# output_8ch_spi_mux.net
KiCad netlist of a schematic drawn in EAGLE
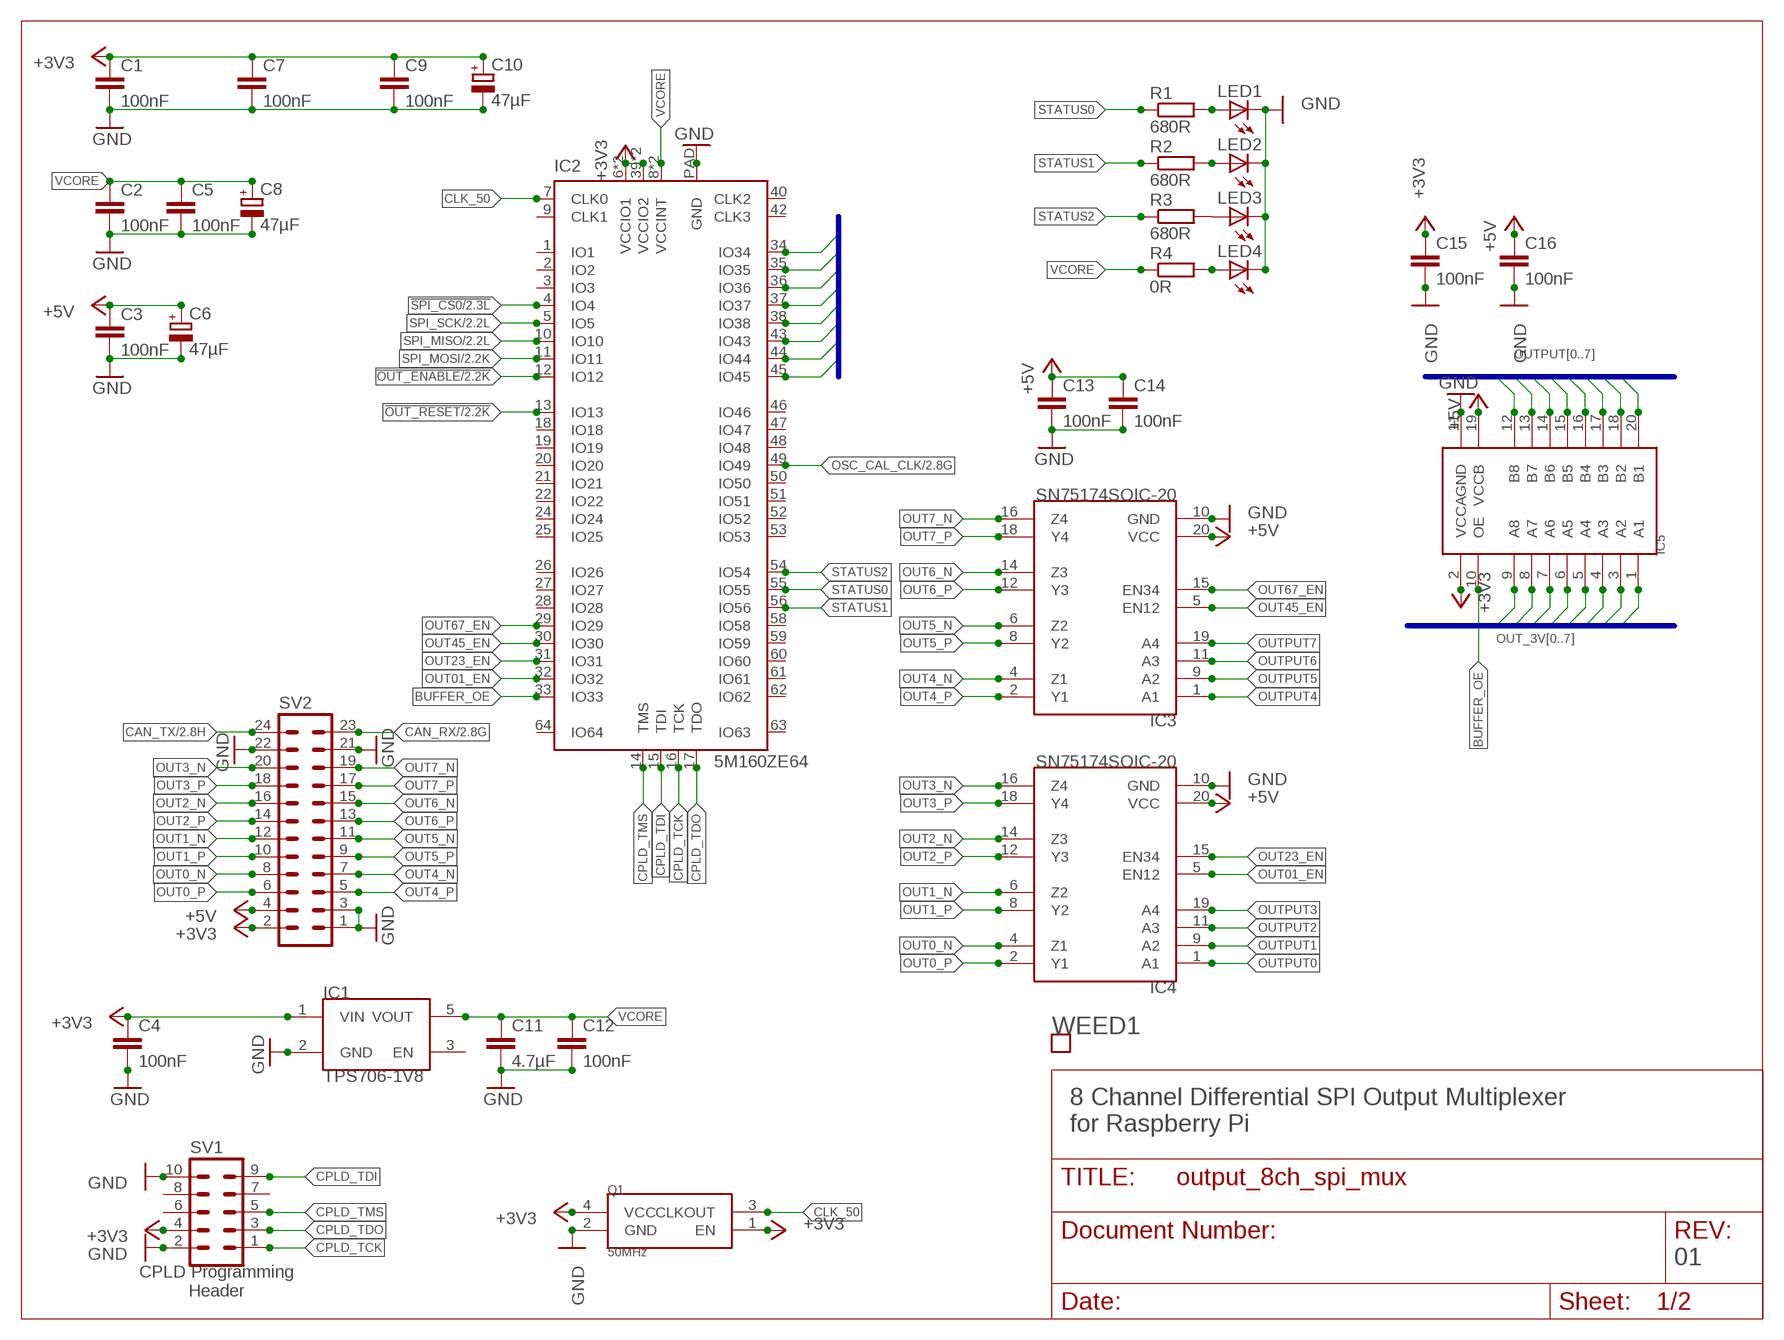
[diagram p0: schematic, sheet 1]
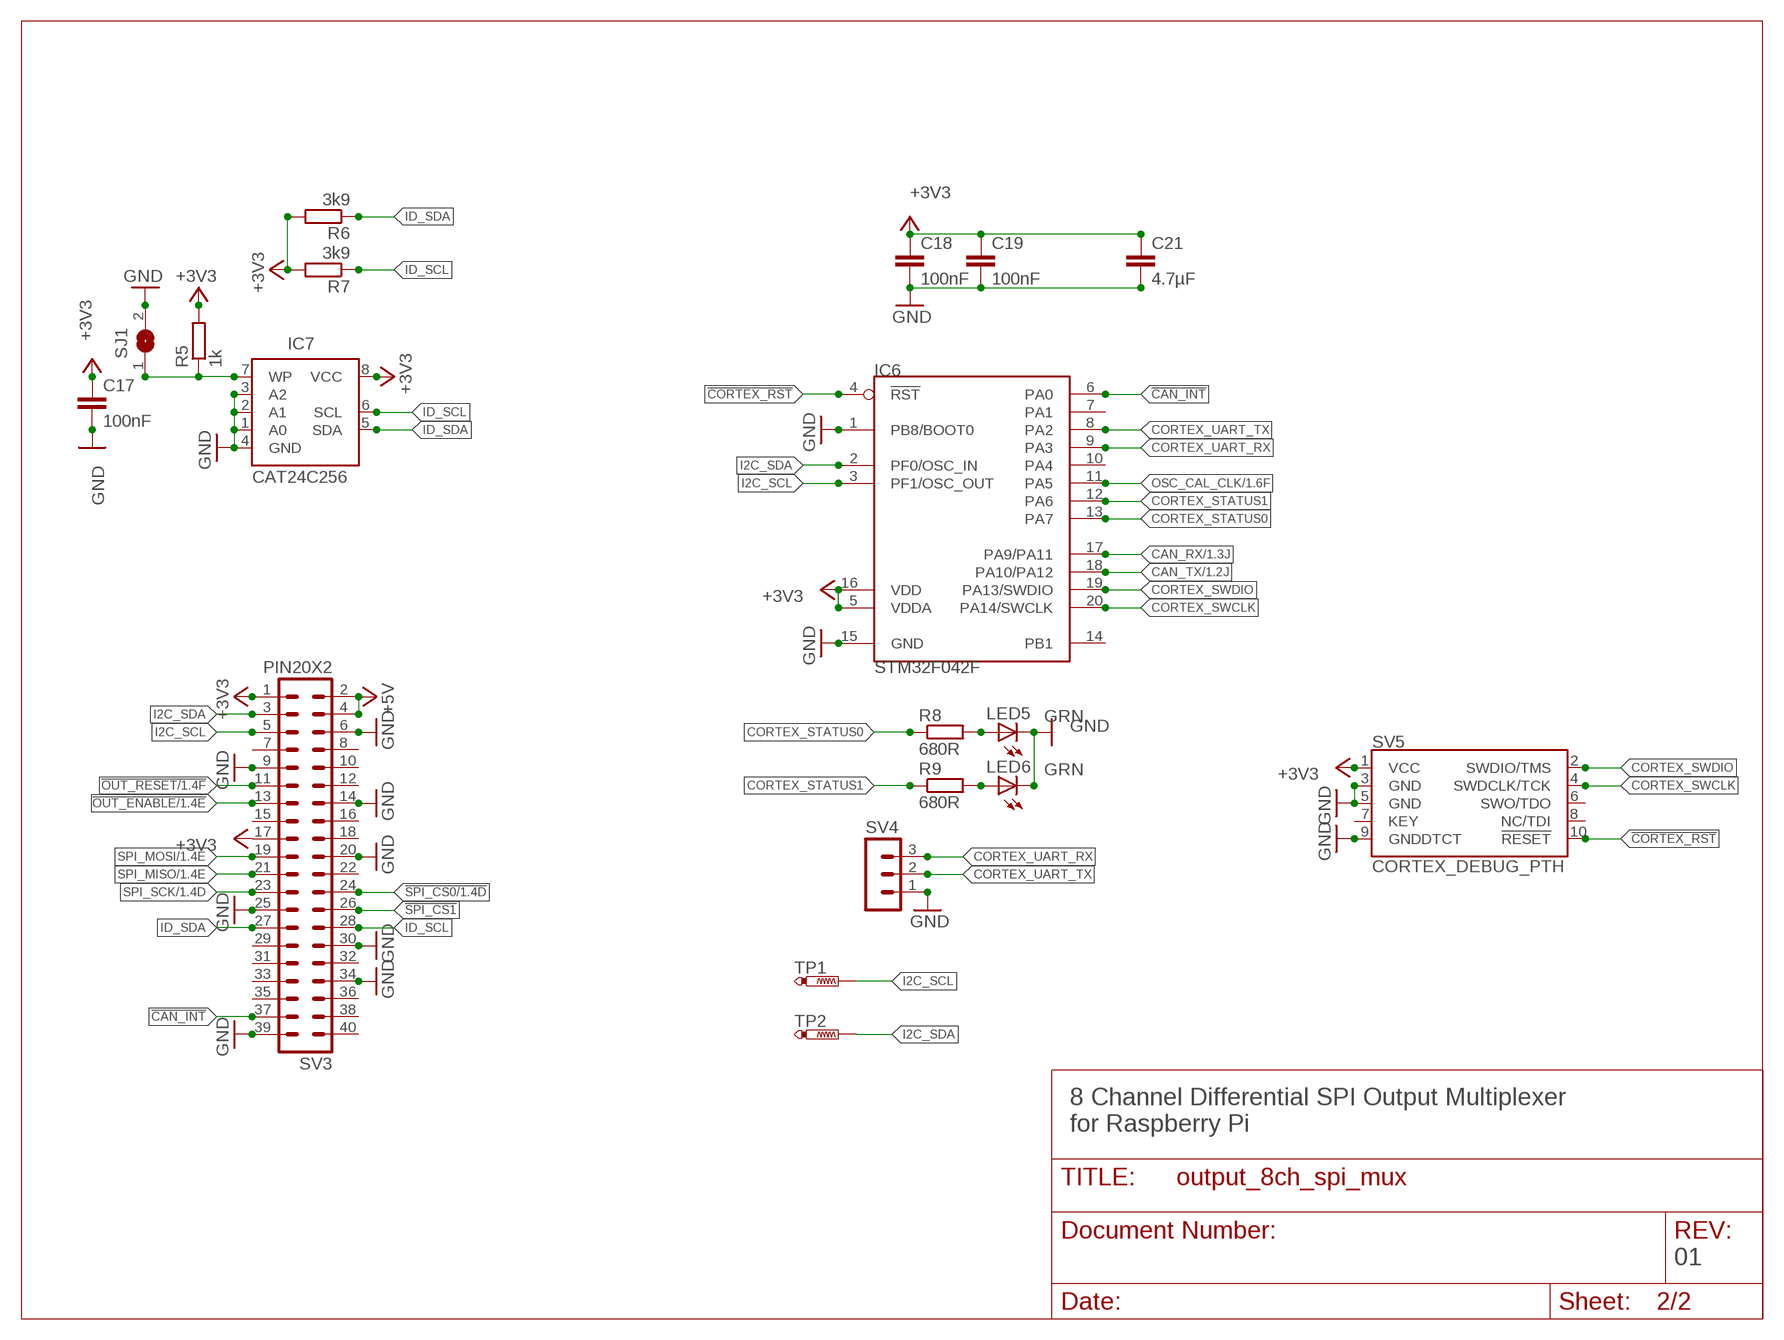
[diagram p1: schematic, sheet 2]

(export (version "E")
  (design (tool "Eeschema 10.0.6"))
  (components
    (comp (ref "C1")
      (value "100nF")
      (footprint "eagle-import:C0805")
      (libsource (lib "eagle-import") (part "C-EUC0805"))
    )
    (comp (ref "C2")
      (value "100nF")
      (footprint "eagle-import:C0805")
      (libsource (lib "eagle-import") (part "C-EUC0805"))
    )
    (comp (ref "C3")
      (value "100nF")
      (footprint "eagle-import:C0805")
      (libsource (lib "eagle-import") (part "C-EUC0805"))
    )
    (comp (ref "C4")
      (value "100nF")
      (footprint "eagle-import:C0805")
      (libsource (lib "eagle-import") (part "C-EUC0805"))
    )
    (comp (ref "C5")
      (value "100nF")
      (footprint "eagle-import:C0805")
      (libsource (lib "eagle-import") (part "C-EUC0805"))
    )
    (comp (ref "C6")
      (value "47µF")
      (footprint "eagle-import:CT6032")
      (libsource (lib "eagle-import") (part "CPOL-EUCT6032"))
    )
    (comp (ref "C7")
      (value "100nF")
      (footprint "eagle-import:C0805")
      (libsource (lib "eagle-import") (part "C-EUC0805"))
    )
    (comp (ref "C8")
      (value "47µF")
      (footprint "eagle-import:CT6032")
      (libsource (lib "eagle-import") (part "CPOL-EUCT6032"))
    )
    (comp (ref "C9")
      (value "100nF")
      (footprint "eagle-import:C0805")
      (libsource (lib "eagle-import") (part "C-EUC0805"))
    )
    (comp (ref "C10")
      (value "47µF")
      (footprint "eagle-import:CT6032")
      (libsource (lib "eagle-import") (part "CPOL-EUCT6032"))
    )
    (comp (ref "C11")
      (value "4.7µF")
      (footprint "eagle-import:C0805")
      (libsource (lib "eagle-import") (part "C-EUC0805"))
    )
    (comp (ref "C12")
      (value "100nF")
      (footprint "eagle-import:C0805")
      (libsource (lib "eagle-import") (part "C-EUC0805"))
    )
    (comp (ref "C13")
      (value "100nF")
      (footprint "eagle-import:C0805")
      (libsource (lib "eagle-import") (part "C-EUC0805"))
    )
    (comp (ref "C14")
      (value "100nF")
      (footprint "eagle-import:C0805")
      (libsource (lib "eagle-import") (part "C-EUC0805"))
    )
    (comp (ref "C15")
      (value "100nF")
      (footprint "eagle-import:C0805")
      (libsource (lib "eagle-import") (part "C-EUC0805"))
    )
    (comp (ref "C16")
      (value "100nF")
      (footprint "eagle-import:C0805")
      (libsource (lib "eagle-import") (part "C-EUC0805"))
    )
    (comp (ref "IC1")
      (value "TPS706-1V8")
      (footprint "eagle-import:SOT23-5")
      (libsource (lib "eagle-import") (part "TPS706SOT23-5"))
    )
    (comp (ref "IC2")
      (value "5M160ZE64")
      (footprint "eagle-import:EQFP64")
      (libsource (lib "eagle-import") (part "5M160ZE64"))
    )
    (comp (ref "IC3")
      (value "SN75174SOIC-20")
      (footprint "eagle-import:SOIC20S")
      (libsource (lib "eagle-import") (part "SN75174SOIC-20"))
    )
    (comp (ref "IC4")
      (value "SN75174SOIC-20")
      (footprint "eagle-import:SOIC20S")
      (libsource (lib "eagle-import") (part "SN75174SOIC-20"))
    )
    (comp (ref "IC5")
      (value "TXB0108TSSOP20")
      (footprint "eagle-import:TSSOP20")
      (libsource (lib "eagle-import") (part "TXB0108TSSOP20"))
    )
    (comp (ref "LED1")
      (value "LEDCHIPLED_1206")
      (footprint "eagle-import:CHIPLED_1206")
      (libsource (lib "eagle-import") (part "LEDCHIPLED_1206"))
    )
    (comp (ref "LED2")
      (value "LEDCHIPLED_1206")
      (footprint "eagle-import:CHIPLED_1206")
      (libsource (lib "eagle-import") (part "LEDCHIPLED_1206"))
    )
    (comp (ref "LED3")
      (value "LEDCHIPLED_1206")
      (footprint "eagle-import:CHIPLED_1206")
      (libsource (lib "eagle-import") (part "LEDCHIPLED_1206"))
    )
    (comp (ref "LED4")
      (value "LEDCHIPLED_1206")
      (footprint "eagle-import:CHIPLED_1206")
      (libsource (lib "eagle-import") (part "LEDCHIPLED_1206"))
    )
    (comp (ref "Q1")
      (value "50MHz")
      (footprint "eagle-import:VLGA-4")
      (libsource (lib "eagle-import") (part "DSC61XX"))
    )
    (comp (ref "R1")
      (value "680R")
      (footprint "eagle-import:M0805")
      (libsource (lib "eagle-import") (part "R-EU_M0805"))
    )
    (comp (ref "R2")
      (value "680R")
      (footprint "eagle-import:M0805")
      (libsource (lib "eagle-import") (part "R-EU_M0805"))
    )
    (comp (ref "R3")
      (value "680R")
      (footprint "eagle-import:M0805")
      (libsource (lib "eagle-import") (part "R-EU_M0805"))
    )
    (comp (ref "R4")
      (value "0R")
      (footprint "eagle-import:M0805")
      (libsource (lib "eagle-import") (part "R-EU_M0805"))
    )
    (comp (ref "SV1")
      (value "MA05-2")
      (footprint "eagle-import:MA05-2")
      (libsource (lib "eagle-import") (part "MA05-2"))
    )
    (comp (ref "SV2")
      (value "MA12-2")
      (footprint "eagle-import:MA12-2")
      (libsource (lib "eagle-import") (part "MA12-2"))
    )
    (comp (ref "WEED1")
      (value "WEED")
      (footprint "eagle-import:DOINK")
      (libsource (lib "eagle-import") (part "WEED"))
    )
    (comp (ref "C17")
      (value "100nF")
      (footprint "eagle-import:C0805")
      (libsource (lib "eagle-import") (part "C-EUC0805"))
    )
    (comp (ref "C18")
      (value "100nF")
      (footprint "eagle-import:C0805")
      (libsource (lib "eagle-import") (part "C-EUC0805"))
    )
    (comp (ref "C19")
      (value "100nF")
      (footprint "eagle-import:C0805")
      (libsource (lib "eagle-import") (part "C-EUC0805"))
    )
    (comp (ref "C21")
      (value "4.7µF")
      (footprint "eagle-import:C0805")
      (libsource (lib "eagle-import") (part "C-EUC0805"))
    )
    (comp (ref "IC6")
      (value "STM32F042F")
      (footprint "eagle-import:TSSOP20")
      (libsource (lib "eagle-import") (part "STM32F042F"))
    )
    (comp (ref "IC7")
      (value "CAT24C256")
      (footprint "eagle-import:SOIC8")
      (libsource (lib "eagle-import") (part "EEPROM24"))
    )
    (comp (ref "LED5")
      (value "GRN")
      (footprint "eagle-import:CHIPLED_1206")
      (libsource (lib "eagle-import") (part "LEDCHIPLED_1206"))
    )
    (comp (ref "LED6")
      (value "GRN")
      (footprint "eagle-import:CHIPLED_1206")
      (libsource (lib "eagle-import") (part "LEDCHIPLED_1206"))
    )
    (comp (ref "R5")
      (value "1k")
      (footprint "eagle-import:M0805")
      (libsource (lib "eagle-import") (part "R-EU_M0805"))
    )
    (comp (ref "R6")
      (value "3k9")
      (footprint "eagle-import:M0805")
      (libsource (lib "eagle-import") (part "R-EU_M0805"))
    )
    (comp (ref "R7")
      (value "3k9")
      (footprint "eagle-import:M0805")
      (libsource (lib "eagle-import") (part "R-EU_M0805"))
    )
    (comp (ref "R8")
      (value "680R")
      (footprint "eagle-import:M0805")
      (libsource (lib "eagle-import") (part "R-EU_M0805"))
    )
    (comp (ref "R9")
      (value "680R")
      (footprint "eagle-import:M0805")
      (libsource (lib "eagle-import") (part "R-EU_M0805"))
    )
    (comp (ref "SJ1") (value "SJ") (footprint "eagle-import:SJ") (libsource (lib "eagle-import") (part "SJ")))
    (comp (ref "SV3")
      (value "PIN20X2")
      (footprint "eagle-import:PIN_20X2")
      (libsource (lib "eagle-import") (part "PIN20X2"))
    )
    (comp (ref "SV4")
      (value "MA03-1")
      (footprint "eagle-import:MA03-1")
      (libsource (lib "eagle-import") (part "MA03-1"))
    )
    (comp (ref "SV5")
      (value "CORTEX_DEBUG_PTH")
      (footprint "eagle-import:2X5-PTH-1.27MM")
      (libsource (lib "eagle-import") (part "CORTEX_DEBUG_PTH"))
    )
    (comp (ref "TP1")
      (value "PTR1B1,27")
      (footprint "eagle-import:B1,27")
      (libsource (lib "eagle-import") (part "PTR1B1,27"))
    )
    (comp (ref "TP2")
      (value "PTR1B1,27")
      (footprint "eagle-import:B1,27")
      (libsource (lib "eagle-import") (part "PTR1B1,27"))
    )
  )
  (nets
    (net (code "1") (name "+3V3") (class "Default")
      (node (ref "C1") (pin "1") (pinfunction "1_1") (pintype "passive"))
      (node (ref "C10") (pin "+") (pinfunction "+_+") (pintype "passive"))
      (node (ref "C15") (pin "1") (pinfunction "1_1") (pintype "passive"))
      (node (ref "C17") (pin "1") (pinfunction "1_1") (pintype "passive"))
      (node (ref "C18") (pin "1") (pinfunction "1_1") (pintype "passive"))
      (node (ref "C19") (pin "1") (pinfunction "1_1") (pintype "passive"))
      (node (ref "C21") (pin "1") (pinfunction "1_1") (pintype "passive"))
      (node (ref "C4") (pin "1") (pinfunction "1_1") (pintype "passive"))
      (node (ref "C7") (pin "1") (pinfunction "1_1") (pintype "passive"))
      (node (ref "C9") (pin "1") (pinfunction "1_1") (pintype "passive"))
      (node (ref "IC1") (pin "1") (pinfunction "VIN_1") (pintype "bidirectional"))
      (node (ref "IC2") (pin "23") (pinfunction "VCCIO1_23") (pintype "power_in"))
      (node (ref "IC2") (pin "39") (pinfunction "VCCIO2_39") (pintype "power_in"))
      (node (ref "IC2") (pin "57") (pinfunction "VCCIO2_57") (pintype "power_in"))
      (node (ref "IC2") (pin "6") (pinfunction "VCCIO1_6") (pintype "power_in"))
      (node (ref "IC5") (pin "2") (pinfunction "VCCA_2") (pintype "bidirectional"))
      (node (ref "IC6") (pin "16") (pinfunction "VDD_16") (pintype "power_in"))
      (node (ref "IC6") (pin "5") (pinfunction "VDDA_5") (pintype "power_in"))
      (node (ref "IC7") (pin "8") (pinfunction "VCC_8") (pintype "power_in"))
      (node (ref "Q1") (pin "1") (pinfunction "EN_1") (pintype "bidirectional"))
      (node (ref "Q1") (pin "4") (pinfunction "VCC_4") (pintype "power_in"))
      (node (ref "R5") (pin "2") (pinfunction "2_2") (pintype "passive"))
      (node (ref "R6") (pin "2") (pinfunction "2_2") (pintype "passive"))
      (node (ref "R7") (pin "2") (pinfunction "2_2") (pintype "passive"))
      (node (ref "SV1") (pin "4") (pinfunction "4_4") (pintype "passive"))
      (node (ref "SV2") (pin "2") (pinfunction "2_2") (pintype "passive"))
      (node (ref "SV3") (pin "1") (pinfunction "1_1") (pintype "passive"))
      (node (ref "SV3") (pin "17") (pinfunction "17_17") (pintype "passive"))
      (node (ref "SV5") (pin "1") (pinfunction "VCC_1") (pintype "bidirectional"))
    )
    (net (code "2") (name "+5V") (class "Default")
      (node (ref "C13") (pin "1") (pinfunction "1_1") (pintype "passive"))
      (node (ref "C14") (pin "1") (pinfunction "1_1") (pintype "passive"))
      (node (ref "C16") (pin "1") (pinfunction "1_1") (pintype "passive"))
      (node (ref "C3") (pin "1") (pinfunction "1_1") (pintype "passive"))
      (node (ref "C6") (pin "+") (pinfunction "+_+") (pintype "passive"))
      (node (ref "IC3") (pin "20") (pinfunction "VCC_20") (pintype "power_in"))
      (node (ref "IC4") (pin "20") (pinfunction "VCC_20") (pintype "power_in"))
      (node (ref "IC5") (pin "19") (pinfunction "VCCB_19") (pintype "bidirectional"))
      (node (ref "SV2") (pin "4") (pinfunction "4_4") (pintype "passive"))
      (node (ref "SV3") (pin "2") (pinfunction "2_2") (pintype "passive"))
      (node (ref "SV3") (pin "4") (pinfunction "4_4") (pintype "passive"))
    )
    (net (code "5") (name "BUFFER_OE") (class "Default")
      (node (ref "IC2") (pin "33") (pinfunction "IO33_33") (pintype "bidirectional"))
      (node (ref "IC5") (pin "10") (pinfunction "OE_10") (pintype "bidirectional"))
    )
    (net (code "6") (name "CAN_RX") (class "Default")
      (node (ref "IC6") (pin "17") (pinfunction "PA9/PA11_17") (pintype "bidirectional"))
      (node (ref "SV2") (pin "23") (pinfunction "23_23") (pintype "passive"))
    )
    (net (code "7") (name "CAN_TX") (class "Default")
      (node (ref "IC6") (pin "18") (pinfunction "PA10/PA12_18") (pintype "bidirectional"))
      (node (ref "SV2") (pin "24") (pinfunction "24_24") (pintype "passive"))
    )
    (net (code "8") (name "CLK_50") (class "Default")
      (node (ref "IC2") (pin "7") (pinfunction "CLK0_7") (pintype "bidirectional"))
      (node (ref "Q1") (pin "3") (pinfunction "CLKOUT_3") (pintype "bidirectional"))
    )
    (net (code "9") (name "CORTEX_STATUS0") (class "Default")
      (node (ref "IC6") (pin "13") (pinfunction "PA7_13") (pintype "bidirectional"))
      (node (ref "R8") (pin "1") (pinfunction "1_1") (pintype "passive"))
    )
    (net (code "10") (name "CORTEX_STATUS1") (class "Default")
      (node (ref "IC6") (pin "12") (pinfunction "PA6_12") (pintype "bidirectional"))
      (node (ref "R9") (pin "1") (pinfunction "1_1") (pintype "passive"))
    )
    (net (code "11") (name "CORTEX_SWCLK") (class "Default")
      (node (ref "IC6") (pin "20") (pinfunction "PA14/SWCLK_20") (pintype "bidirectional"))
      (node (ref "SV5") (pin "4") (pinfunction "SWDCLK/TCK_4") (pintype "bidirectional"))
    )
    (net (code "12") (name "CORTEX_SWDIO") (class "Default")
      (node (ref "IC6") (pin "19") (pinfunction "PA13/SWDIO_19") (pintype "bidirectional"))
      (node (ref "SV5") (pin "2") (pinfunction "SWDIO/TMS_2") (pintype "bidirectional"))
    )
    (net (code "13") (name "CORTEX_UART_RX") (class "Default")
      (node (ref "IC6") (pin "9") (pinfunction "PA3_9") (pintype "bidirectional"))
      (node (ref "SV4") (pin "3") (pinfunction "3_3") (pintype "passive"))
    )
    (net (code "14") (name "CORTEX_UART_TX") (class "Default")
      (node (ref "IC6") (pin "8") (pinfunction "PA2_8") (pintype "bidirectional"))
      (node (ref "SV4") (pin "2") (pinfunction "2_2") (pintype "passive"))
    )
    (net (code "15") (name "CPLD_TCK") (class "Default")
      (node (ref "IC2") (pin "16") (pinfunction "TCK_16") (pintype "input"))
      (node (ref "SV1") (pin "1") (pinfunction "1_1") (pintype "passive"))
    )
    (net (code "16") (name "CPLD_TDI") (class "Default")
      (node (ref "IC2") (pin "15") (pinfunction "TDI_15") (pintype "input"))
      (node (ref "SV1") (pin "9") (pinfunction "9_9") (pintype "passive"))
    )
    (net (code "17") (name "CPLD_TDO") (class "Default")
      (node (ref "IC2") (pin "17") (pinfunction "TDO_17") (pintype "output"))
      (node (ref "SV1") (pin "3") (pinfunction "3_3") (pintype "passive"))
    )
    (net (code "18") (name "CPLD_TMS") (class "Default")
      (node (ref "IC2") (pin "14") (pinfunction "TMS_14") (pintype "input"))
      (node (ref "SV1") (pin "5") (pinfunction "5_5") (pintype "passive"))
    )
    (net (code "19") (name "GND") (class "Default")
      (node (ref "C1") (pin "2") (pinfunction "2_2") (pintype "passive"))
      (node (ref "C10") (pin "-") (pinfunction "-_-") (pintype "passive"))
      (node (ref "C11") (pin "2") (pinfunction "2_2") (pintype "passive"))
      (node (ref "C12") (pin "2") (pinfunction "2_2") (pintype "passive"))
      (node (ref "C13") (pin "2") (pinfunction "2_2") (pintype "passive"))
      (node (ref "C14") (pin "2") (pinfunction "2_2") (pintype "passive"))
      (node (ref "C15") (pin "2") (pinfunction "2_2") (pintype "passive"))
      (node (ref "C16") (pin "2") (pinfunction "2_2") (pintype "passive"))
      (node (ref "C17") (pin "2") (pinfunction "2_2") (pintype "passive"))
      (node (ref "C18") (pin "2") (pinfunction "2_2") (pintype "passive"))
      (node (ref "C19") (pin "2") (pinfunction "2_2") (pintype "passive"))
      (node (ref "C2") (pin "2") (pinfunction "2_2") (pintype "passive"))
      (node (ref "C21") (pin "2") (pinfunction "2_2") (pintype "passive"))
      (node (ref "C3") (pin "2") (pinfunction "2_2") (pintype "passive"))
      (node (ref "C4") (pin "2") (pinfunction "2_2") (pintype "passive"))
      (node (ref "C5") (pin "2") (pinfunction "2_2") (pintype "passive"))
      (node (ref "C6") (pin "-") (pinfunction "-_-") (pintype "passive"))
      (node (ref "C7") (pin "2") (pinfunction "2_2") (pintype "passive"))
      (node (ref "C8") (pin "-") (pinfunction "-_-") (pintype "passive"))
      (node (ref "C9") (pin "2") (pinfunction "2_2") (pintype "passive"))
      (node (ref "IC1") (pin "2") (pinfunction "GND_2") (pintype "bidirectional"))
      (node (ref "IC2") (pin "PAD") (pinfunction "GND_PAD") (pintype "power_in"))
      (node (ref "IC3") (pin "10") (pinfunction "GND_10") (pintype "power_in"))
      (node (ref "IC4") (pin "10") (pinfunction "GND_10") (pintype "power_in"))
      (node (ref "IC5") (pin "11") (pinfunction "GND_11") (pintype "bidirectional"))
      (node (ref "IC6") (pin "1") (pinfunction "PB8/BOOT0_1") (pintype "bidirectional"))
      (node (ref "IC6") (pin "15") (pinfunction "GND_15") (pintype "power_in"))
      (node (ref "IC7") (pin "1") (pinfunction "A0_1") (pintype "input"))
      (node (ref "IC7") (pin "2") (pinfunction "A1_2") (pintype "input"))
      (node (ref "IC7") (pin "3") (pinfunction "A2_3") (pintype "input"))
      (node (ref "IC7") (pin "4") (pinfunction "GND_4") (pintype "power_in"))
      (node (ref "LED1") (pin "C") (pinfunction "C_C") (pintype "passive"))
      (node (ref "LED2") (pin "C") (pinfunction "C_C") (pintype "passive"))
      (node (ref "LED3") (pin "C") (pinfunction "C_C") (pintype "passive"))
      (node (ref "LED4") (pin "C") (pinfunction "C_C") (pintype "passive"))
      (node (ref "LED5") (pin "C") (pinfunction "C_C") (pintype "passive"))
      (node (ref "LED6") (pin "C") (pinfunction "C_C") (pintype "passive"))
      (node (ref "Q1") (pin "2") (pinfunction "GND_2") (pintype "power_in"))
      (node (ref "SJ1") (pin "2") (pinfunction "2_2") (pintype "passive"))
      (node (ref "SV1") (pin "10") (pinfunction "10_10") (pintype "passive"))
      (node (ref "SV1") (pin "2") (pinfunction "2_2") (pintype "passive"))
      (node (ref "SV2") (pin "1") (pinfunction "1_1") (pintype "passive"))
      (node (ref "SV2") (pin "21") (pinfunction "21_21") (pintype "passive"))
      (node (ref "SV2") (pin "22") (pinfunction "22_22") (pintype "passive"))
      (node (ref "SV2") (pin "3") (pinfunction "3_3") (pintype "passive"))
      (node (ref "SV3") (pin "14") (pinfunction "14_14") (pintype "passive"))
      (node (ref "SV3") (pin "20") (pinfunction "20_20") (pintype "passive"))
      (node (ref "SV3") (pin "25") (pinfunction "25_25") (pintype "passive"))
      (node (ref "SV3") (pin "30") (pinfunction "30_30") (pintype "passive"))
      (node (ref "SV3") (pin "34") (pinfunction "34_34") (pintype "passive"))
      (node (ref "SV3") (pin "39") (pinfunction "39_39") (pintype "passive"))
      (node (ref "SV3") (pin "6") (pinfunction "6_6") (pintype "passive"))
      (node (ref "SV3") (pin "9") (pinfunction "9_9") (pintype "passive"))
      (node (ref "SV4") (pin "1") (pinfunction "1_1") (pintype "passive"))
      (node (ref "SV5") (pin "3") (pinfunction "GND_3") (pintype "bidirectional"))
      (node (ref "SV5") (pin "5") (pinfunction "GND_5") (pintype "bidirectional"))
      (node (ref "SV5") (pin "9") (pinfunction "GNDDTCT_9") (pintype "bidirectional"))
    )
    (net (code "20") (name "I2C_SCL") (class "Default")
      (node (ref "IC6") (pin "3") (pinfunction "PF1/OSC_OUT_3") (pintype "bidirectional"))
      (node (ref "SV3") (pin "5") (pinfunction "5_5") (pintype "passive"))
      (node (ref "TP1") (pin "TP") (pinfunction "TP_TP") (pintype "input"))
    )
    (net (code "21") (name "I2C_SDA") (class "Default")
      (node (ref "IC6") (pin "2") (pinfunction "PF0/OSC_IN_2") (pintype "bidirectional"))
      (node (ref "SV3") (pin "3") (pinfunction "3_3") (pintype "passive"))
      (node (ref "TP2") (pin "TP") (pinfunction "TP_TP") (pintype "input"))
    )
    (net (code "22") (name "ID_SCL") (class "Default")
      (node (ref "IC7") (pin "6") (pinfunction "SCL_6") (pintype "input"))
      (node (ref "R7") (pin "1") (pinfunction "1_1") (pintype "passive"))
      (node (ref "SV3") (pin "28") (pinfunction "28_28") (pintype "passive"))
    )
    (net (code "23") (name "ID_SDA") (class "Default")
      (node (ref "IC7") (pin "5") (pinfunction "SDA_5") (pintype "bidirectional"))
      (node (ref "R6") (pin "1") (pinfunction "1_1") (pintype "passive"))
      (node (ref "SV3") (pin "27") (pinfunction "27_27") (pintype "passive"))
    )
    (net (code "24") (name "Net-(IC7-WP)") (class "Default")
      (node (ref "IC7") (pin "7") (pinfunction "WP_7") (pintype "input"))
      (node (ref "R5") (pin "1") (pinfunction "1_1") (pintype "passive"))
      (node (ref "SJ1") (pin "1") (pinfunction "1_1") (pintype "passive"))
    )
    (net (code "25") (name "Net-(LED1-PadA)") (class "Default")
      (node (ref "LED1") (pin "A") (pinfunction "A_A") (pintype "passive"))
      (node (ref "R1") (pin "2") (pinfunction "2_2") (pintype "passive"))
    )
    (net (code "26") (name "Net-(LED2-PadA)") (class "Default")
      (node (ref "LED2") (pin "A") (pinfunction "A_A") (pintype "passive"))
      (node (ref "R2") (pin "2") (pinfunction "2_2") (pintype "passive"))
    )
    (net (code "27") (name "Net-(LED3-PadA)") (class "Default")
      (node (ref "LED3") (pin "A") (pinfunction "A_A") (pintype "passive"))
      (node (ref "R3") (pin "2") (pinfunction "2_2") (pintype "passive"))
    )
    (net (code "28") (name "Net-(LED4-PadA)") (class "Default")
      (node (ref "LED4") (pin "A") (pinfunction "A_A") (pintype "passive"))
      (node (ref "R4") (pin "2") (pinfunction "2_2") (pintype "passive"))
    )
    (net (code "29") (name "Net-(LED5-PadA)") (class "Default")
      (node (ref "LED5") (pin "A") (pinfunction "A_A") (pintype "passive"))
      (node (ref "R8") (pin "2") (pinfunction "2_2") (pintype "passive"))
    )
    (net (code "30") (name "Net-(LED6-PadA)") (class "Default")
      (node (ref "LED6") (pin "A") (pinfunction "A_A") (pintype "passive"))
      (node (ref "R9") (pin "2") (pinfunction "2_2") (pintype "passive"))
    )
    (net (code "31") (name "OSC_CAL_CLK") (class "Default")
      (node (ref "IC2") (pin "49") (pinfunction "IO49_49") (pintype "bidirectional"))
      (node (ref "IC6") (pin "11") (pinfunction "PA5_11") (pintype "bidirectional"))
    )
    (net (code "32") (name "OUT0_N") (class "Default")
      (node (ref "IC4") (pin "4") (pinfunction "Z1_4") (pintype "output"))
      (node (ref "SV2") (pin "8") (pinfunction "8_8") (pintype "passive"))
    )
    (net (code "33") (name "OUT0_P") (class "Default")
      (node (ref "IC4") (pin "2") (pinfunction "Y1_2") (pintype "output"))
      (node (ref "SV2") (pin "6") (pinfunction "6_6") (pintype "passive"))
    )
    (net (code "34") (name "OUT01_EN") (class "Default")
      (node (ref "IC2") (pin "32") (pinfunction "IO32_32") (pintype "bidirectional"))
      (node (ref "IC4") (pin "5") (pinfunction "EN12_5") (pintype "input"))
    )
    (net (code "35") (name "OUT1_N") (class "Default")
      (node (ref "IC4") (pin "6") (pinfunction "Z2_6") (pintype "output"))
      (node (ref "SV2") (pin "12") (pinfunction "12_12") (pintype "passive"))
    )
    (net (code "36") (name "OUT1_P") (class "Default")
      (node (ref "IC4") (pin "8") (pinfunction "Y2_8") (pintype "output"))
      (node (ref "SV2") (pin "10") (pinfunction "10_10") (pintype "passive"))
    )
    (net (code "37") (name "OUT2_N") (class "Default")
      (node (ref "IC4") (pin "14") (pinfunction "Z3_14") (pintype "output"))
      (node (ref "SV2") (pin "16") (pinfunction "16_16") (pintype "passive"))
    )
    (net (code "38") (name "OUT2_P") (class "Default")
      (node (ref "IC4") (pin "12") (pinfunction "Y3_12") (pintype "output"))
      (node (ref "SV2") (pin "14") (pinfunction "14_14") (pintype "passive"))
    )
    (net (code "39") (name "OUT3_N") (class "Default")
      (node (ref "IC4") (pin "16") (pinfunction "Z4_16") (pintype "output"))
      (node (ref "SV2") (pin "20") (pinfunction "20_20") (pintype "passive"))
    )
    (net (code "40") (name "OUT3_P") (class "Default")
      (node (ref "IC4") (pin "18") (pinfunction "Y4_18") (pintype "output"))
      (node (ref "SV2") (pin "18") (pinfunction "18_18") (pintype "passive"))
    )
    (net (code "41") (name "OUT4_N") (class "Default")
      (node (ref "IC3") (pin "4") (pinfunction "Z1_4") (pintype "output"))
      (node (ref "SV2") (pin "7") (pinfunction "7_7") (pintype "passive"))
    )
    (net (code "42") (name "OUT4_P") (class "Default")
      (node (ref "IC3") (pin "2") (pinfunction "Y1_2") (pintype "output"))
      (node (ref "SV2") (pin "5") (pinfunction "5_5") (pintype "passive"))
    )
    (net (code "43") (name "OUT5_N") (class "Default")
      (node (ref "IC3") (pin "6") (pinfunction "Z2_6") (pintype "output"))
      (node (ref "SV2") (pin "11") (pinfunction "11_11") (pintype "passive"))
    )
    (net (code "44") (name "OUT5_P") (class "Default")
      (node (ref "IC3") (pin "8") (pinfunction "Y2_8") (pintype "output"))
      (node (ref "SV2") (pin "9") (pinfunction "9_9") (pintype "passive"))
    )
    (net (code "45") (name "OUT6_N") (class "Default")
      (node (ref "IC3") (pin "14") (pinfunction "Z3_14") (pintype "output"))
      (node (ref "SV2") (pin "15") (pinfunction "15_15") (pintype "passive"))
    )
    (net (code "46") (name "OUT6_P") (class "Default")
      (node (ref "IC3") (pin "12") (pinfunction "Y3_12") (pintype "output"))
      (node (ref "SV2") (pin "13") (pinfunction "13_13") (pintype "passive"))
    )
    (net (code "47") (name "OUT7_N") (class "Default")
      (node (ref "IC3") (pin "16") (pinfunction "Z4_16") (pintype "output"))
      (node (ref "SV2") (pin "19") (pinfunction "19_19") (pintype "passive"))
    )
    (net (code "48") (name "OUT7_P") (class "Default")
      (node (ref "IC3") (pin "18") (pinfunction "Y4_18") (pintype "output"))
      (node (ref "SV2") (pin "17") (pinfunction "17_17") (pintype "passive"))
    )
    (net (code "49") (name "OUT23_EN") (class "Default")
      (node (ref "IC2") (pin "31") (pinfunction "IO31_31") (pintype "bidirectional"))
      (node (ref "IC4") (pin "15") (pinfunction "EN34_15") (pintype "input"))
    )
    (net (code "50") (name "OUT45_EN") (class "Default")
      (node (ref "IC2") (pin "30") (pinfunction "IO30_30") (pintype "bidirectional"))
      (node (ref "IC3") (pin "5") (pinfunction "EN12_5") (pintype "input"))
    )
    (net (code "51") (name "OUT67_EN") (class "Default")
      (node (ref "IC2") (pin "29") (pinfunction "IO29_29") (pintype "bidirectional"))
      (node (ref "IC3") (pin "15") (pinfunction "EN34_15") (pintype "input"))
    )
    (net (code "52") (name "OUTPUT0") (class "Default")
      (node (ref "IC4") (pin "1") (pinfunction "A1_1") (pintype "input"))
      (node (ref "IC5") (pin "20") (pinfunction "B1_20") (pintype "bidirectional"))
    )
    (net (code "53") (name "OUTPUT1") (class "Default")
      (node (ref "IC4") (pin "9") (pinfunction "A2_9") (pintype "input"))
      (node (ref "IC5") (pin "18") (pinfunction "B2_18") (pintype "bidirectional"))
    )
    (net (code "54") (name "OUTPUT2") (class "Default")
      (node (ref "IC4") (pin "11") (pinfunction "A3_11") (pintype "input"))
      (node (ref "IC5") (pin "17") (pinfunction "B3_17") (pintype "bidirectional"))
    )
    (net (code "55") (name "OUTPUT3") (class "Default")
      (node (ref "IC4") (pin "19") (pinfunction "A4_19") (pintype "input"))
      (node (ref "IC5") (pin "16") (pinfunction "B4_16") (pintype "bidirectional"))
    )
    (net (code "56") (name "OUTPUT4") (class "Default")
      (node (ref "IC3") (pin "1") (pinfunction "A1_1") (pintype "input"))
      (node (ref "IC5") (pin "15") (pinfunction "B5_15") (pintype "bidirectional"))
    )
    (net (code "57") (name "OUTPUT5") (class "Default")
      (node (ref "IC3") (pin "9") (pinfunction "A2_9") (pintype "input"))
      (node (ref "IC5") (pin "14") (pinfunction "B6_14") (pintype "bidirectional"))
    )
    (net (code "58") (name "OUTPUT6") (class "Default")
      (node (ref "IC3") (pin "11") (pinfunction "A3_11") (pintype "input"))
      (node (ref "IC5") (pin "13") (pinfunction "B7_13") (pintype "bidirectional"))
    )
    (net (code "59") (name "OUTPUT7") (class "Default")
      (node (ref "IC3") (pin "19") (pinfunction "A4_19") (pintype "input"))
      (node (ref "IC5") (pin "12") (pinfunction "B8_12") (pintype "bidirectional"))
    )
    (net (code "60") (name "OUT_3V0") (class "Default")
      (node (ref "IC2") (pin "45") (pinfunction "IO45_45") (pintype "bidirectional"))
      (node (ref "IC5") (pin "1") (pinfunction "A1_1") (pintype "bidirectional"))
    )
    (net (code "61") (name "OUT_3V1") (class "Default")
      (node (ref "IC2") (pin "44") (pinfunction "IO44_44") (pintype "bidirectional"))
      (node (ref "IC5") (pin "3") (pinfunction "A2_3") (pintype "bidirectional"))
    )
    (net (code "62") (name "OUT_3V2") (class "Default")
      (node (ref "IC2") (pin "43") (pinfunction "IO43_43") (pintype "bidirectional"))
      (node (ref "IC5") (pin "4") (pinfunction "A3_4") (pintype "bidirectional"))
    )
    (net (code "63") (name "OUT_3V3") (class "Default")
      (node (ref "IC2") (pin "38") (pinfunction "IO38_38") (pintype "bidirectional"))
      (node (ref "IC5") (pin "5") (pinfunction "A4_5") (pintype "bidirectional"))
    )
    (net (code "64") (name "OUT_3V4") (class "Default")
      (node (ref "IC2") (pin "37") (pinfunction "IO37_37") (pintype "bidirectional"))
      (node (ref "IC5") (pin "6") (pinfunction "A5_6") (pintype "bidirectional"))
    )
    (net (code "65") (name "OUT_3V5") (class "Default")
      (node (ref "IC2") (pin "36") (pinfunction "IO36_36") (pintype "bidirectional"))
      (node (ref "IC5") (pin "7") (pinfunction "A6_7") (pintype "bidirectional"))
    )
    (net (code "66") (name "OUT_3V6") (class "Default")
      (node (ref "IC2") (pin "35") (pinfunction "IO35_35") (pintype "bidirectional"))
      (node (ref "IC5") (pin "8") (pinfunction "A7_8") (pintype "bidirectional"))
    )
    (net (code "67") (name "OUT_3V7") (class "Default")
      (node (ref "IC2") (pin "34") (pinfunction "IO34_34") (pintype "bidirectional"))
      (node (ref "IC5") (pin "9") (pinfunction "A8_9") (pintype "bidirectional"))
    )
    (net (code "68") (name "SPI_MISO") (class "Default")
      (node (ref "IC2") (pin "10") (pinfunction "IO10_10") (pintype "bidirectional"))
      (node (ref "SV3") (pin "21") (pinfunction "21_21") (pintype "passive"))
    )
    (net (code "69") (name "SPI_MOSI") (class "Default")
      (node (ref "IC2") (pin "11") (pinfunction "IO11_11") (pintype "bidirectional"))
      (node (ref "SV3") (pin "19") (pinfunction "19_19") (pintype "passive"))
    )
    (net (code "70") (name "SPI_SCK") (class "Default")
      (node (ref "IC2") (pin "5") (pinfunction "IO5_5") (pintype "bidirectional"))
      (node (ref "SV3") (pin "23") (pinfunction "23_23") (pintype "passive"))
    )
    (net (code "71") (name "STATUS0") (class "Default")
      (node (ref "IC2") (pin "55") (pinfunction "IO55_55") (pintype "bidirectional"))
      (node (ref "R1") (pin "1") (pinfunction "1_1") (pintype "passive"))
    )
    (net (code "72") (name "STATUS1") (class "Default")
      (node (ref "IC2") (pin "56") (pinfunction "IO56_56") (pintype "bidirectional"))
      (node (ref "R2") (pin "1") (pinfunction "1_1") (pintype "passive"))
    )
    (net (code "73") (name "STATUS2") (class "Default")
      (node (ref "IC2") (pin "54") (pinfunction "IO54_54") (pintype "bidirectional"))
      (node (ref "R3") (pin "1") (pinfunction "1_1") (pintype "passive"))
    )
    (net (code "74") (name "VCORE") (class "Default")
      (node (ref "C11") (pin "1") (pinfunction "1_1") (pintype "passive"))
      (node (ref "C12") (pin "1") (pinfunction "1_1") (pintype "passive"))
      (node (ref "C2") (pin "1") (pinfunction "1_1") (pintype "passive"))
      (node (ref "C5") (pin "1") (pinfunction "1_1") (pintype "passive"))
      (node (ref "C8") (pin "+") (pinfunction "+_+") (pintype "passive"))
      (node (ref "IC1") (pin "5") (pinfunction "VOUT_5") (pintype "bidirectional"))
      (node (ref "IC2") (pin "41") (pinfunction "VCCINT_41") (pintype "power_in"))
      (node (ref "IC2") (pin "8") (pinfunction "VCCINT_8") (pintype "power_in"))
      (node (ref "R4") (pin "1") (pinfunction "1_1") (pintype "passive"))
    )
    (net (code "75") (name "unconnected-(IC1-EN-Pad3)") (class "Default")
      (node (ref "IC1") (pin "3") (pinfunction "EN_3") (pintype "bidirectional"))
    )
    (net (code "76") (name "unconnected-(IC2-CLK1-Pad9)") (class "Default")
      (node (ref "IC2") (pin "9") (pinfunction "CLK1_9") (pintype "bidirectional"))
    )
    (net (code "77") (name "unconnected-(IC2-CLK2-Pad40)") (class "Default")
      (node (ref "IC2") (pin "40") (pinfunction "CLK2_40") (pintype "bidirectional"))
    )
    (net (code "78") (name "unconnected-(IC2-CLK3-Pad42)") (class "Default")
      (node (ref "IC2") (pin "42") (pinfunction "CLK3_42") (pintype "bidirectional"))
    )
    (net (code "79") (name "unconnected-(IC2-IO1-Pad1)") (class "Default")
      (node (ref "IC2") (pin "1") (pinfunction "IO1_1") (pintype "bidirectional"))
    )
    (net (code "80") (name "unconnected-(IC2-IO2-Pad2)") (class "Default")
      (node (ref "IC2") (pin "2") (pinfunction "IO2_2") (pintype "bidirectional"))
    )
    (net (code "81") (name "unconnected-(IC2-IO3-Pad3)") (class "Default")
      (node (ref "IC2") (pin "3") (pinfunction "IO3_3") (pintype "bidirectional"))
    )
    (net (code "82") (name "unconnected-(IC2-IO18-Pad18)") (class "Default")
      (node (ref "IC2") (pin "18") (pinfunction "IO18_18") (pintype "bidirectional"))
    )
    (net (code "83") (name "unconnected-(IC2-IO19-Pad19)") (class "Default")
      (node (ref "IC2") (pin "19") (pinfunction "IO19_19") (pintype "bidirectional"))
    )
    (net (code "84") (name "unconnected-(IC2-IO20-Pad20)") (class "Default")
      (node (ref "IC2") (pin "20") (pinfunction "IO20_20") (pintype "bidirectional"))
    )
    (net (code "85") (name "unconnected-(IC2-IO21-Pad21)") (class "Default")
      (node (ref "IC2") (pin "21") (pinfunction "IO21_21") (pintype "bidirectional"))
    )
    (net (code "86") (name "unconnected-(IC2-IO22-Pad22)") (class "Default")
      (node (ref "IC2") (pin "22") (pinfunction "IO22_22") (pintype "bidirectional"))
    )
    (net (code "87") (name "unconnected-(IC2-IO24-Pad24)") (class "Default")
      (node (ref "IC2") (pin "24") (pinfunction "IO24_24") (pintype "bidirectional"))
    )
    (net (code "88") (name "unconnected-(IC2-IO25-Pad25)") (class "Default")
      (node (ref "IC2") (pin "25") (pinfunction "IO25_25") (pintype "bidirectional"))
    )
    (net (code "89") (name "unconnected-(IC2-IO26-Pad26)") (class "Default")
      (node (ref "IC2") (pin "26") (pinfunction "IO26_26") (pintype "bidirectional"))
    )
    (net (code "90") (name "unconnected-(IC2-IO27-Pad27)") (class "Default")
      (node (ref "IC2") (pin "27") (pinfunction "IO27_27") (pintype "bidirectional"))
    )
    (net (code "91") (name "unconnected-(IC2-IO28-Pad28)") (class "Default")
      (node (ref "IC2") (pin "28") (pinfunction "IO28_28") (pintype "bidirectional"))
    )
    (net (code "92") (name "unconnected-(IC2-IO46-Pad46)") (class "Default")
      (node (ref "IC2") (pin "46") (pinfunction "IO46_46") (pintype "bidirectional"))
    )
    (net (code "93") (name "unconnected-(IC2-IO47-Pad47)") (class "Default")
      (node (ref "IC2") (pin "47") (pinfunction "IO47_47") (pintype "bidirectional"))
    )
    (net (code "94") (name "unconnected-(IC2-IO48-Pad48)") (class "Default")
      (node (ref "IC2") (pin "48") (pinfunction "IO48_48") (pintype "bidirectional"))
    )
    (net (code "95") (name "unconnected-(IC2-IO50-Pad50)") (class "Default")
      (node (ref "IC2") (pin "50") (pinfunction "IO50_50") (pintype "bidirectional"))
    )
    (net (code "96") (name "unconnected-(IC2-IO51-Pad51)") (class "Default")
      (node (ref "IC2") (pin "51") (pinfunction "IO51_51") (pintype "bidirectional"))
    )
    (net (code "97") (name "unconnected-(IC2-IO52-Pad52)") (class "Default")
      (node (ref "IC2") (pin "52") (pinfunction "IO52_52") (pintype "bidirectional"))
    )
    (net (code "98") (name "unconnected-(IC2-IO53-Pad53)") (class "Default")
      (node (ref "IC2") (pin "53") (pinfunction "IO53_53") (pintype "bidirectional"))
    )
    (net (code "99") (name "unconnected-(IC2-IO58-Pad58)") (class "Default")
      (node (ref "IC2") (pin "58") (pinfunction "IO58_58") (pintype "bidirectional"))
    )
    (net (code "100") (name "unconnected-(IC2-IO59-Pad59)") (class "Default")
      (node (ref "IC2") (pin "59") (pinfunction "IO59_59") (pintype "bidirectional"))
    )
    (net (code "101") (name "unconnected-(IC2-IO60-Pad60)") (class "Default")
      (node (ref "IC2") (pin "60") (pinfunction "IO60_60") (pintype "bidirectional"))
    )
    (net (code "102") (name "unconnected-(IC2-IO61-Pad61)") (class "Default")
      (node (ref "IC2") (pin "61") (pinfunction "IO61_61") (pintype "bidirectional"))
    )
    (net (code "103") (name "unconnected-(IC2-IO62-Pad62)") (class "Default")
      (node (ref "IC2") (pin "62") (pinfunction "IO62_62") (pintype "bidirectional"))
    )
    (net (code "104") (name "unconnected-(IC2-IO63-Pad63)") (class "Default")
      (node (ref "IC2") (pin "63") (pinfunction "IO63_63") (pintype "bidirectional"))
    )
    (net (code "105") (name "unconnected-(IC2-IO64-Pad64)") (class "Default")
      (node (ref "IC2") (pin "64") (pinfunction "IO64_64") (pintype "bidirectional"))
    )
    (net (code "106") (name "unconnected-(IC6-PA1-Pad7)") (class "Default")
      (node (ref "IC6") (pin "7") (pinfunction "PA1_7") (pintype "bidirectional"))
    )
    (net (code "107") (name "unconnected-(IC6-PA4-Pad10)") (class "Default")
      (node (ref "IC6") (pin "10") (pinfunction "PA4_10") (pintype "bidirectional"))
    )
    (net (code "108") (name "unconnected-(IC6-PB1-Pad14)") (class "Default")
      (node (ref "IC6") (pin "14") (pinfunction "PB1_14") (pintype "bidirectional"))
    )
    (net (code "109") (name "unconnected-(SV1-Pad6)") (class "Default")
      (node (ref "SV1") (pin "6") (pinfunction "6_6") (pintype "passive"))
    )
    (net (code "110") (name "unconnected-(SV1-Pad7)") (class "Default")
      (node (ref "SV1") (pin "7") (pinfunction "7_7") (pintype "passive"))
    )
    (net (code "111") (name "unconnected-(SV1-Pad8)") (class "Default")
      (node (ref "SV1") (pin "8") (pinfunction "8_8") (pintype "passive"))
    )
    (net (code "112") (name "unconnected-(SV3-Pad7)") (class "Default")
      (node (ref "SV3") (pin "7") (pinfunction "7_7") (pintype "passive"))
    )
    (net (code "113") (name "unconnected-(SV3-Pad8)") (class "Default")
      (node (ref "SV3") (pin "8") (pinfunction "8_8") (pintype "passive"))
    )
    (net (code "114") (name "unconnected-(SV3-Pad10)") (class "Default")
      (node (ref "SV3") (pin "10") (pinfunction "10_10") (pintype "passive"))
    )
    (net (code "115") (name "unconnected-(SV3-Pad12)") (class "Default")
      (node (ref "SV3") (pin "12") (pinfunction "12_12") (pintype "passive"))
    )
    (net (code "116") (name "unconnected-(SV3-Pad15)") (class "Default")
      (node (ref "SV3") (pin "15") (pinfunction "15_15") (pintype "passive"))
    )
    (net (code "117") (name "unconnected-(SV3-Pad16)") (class "Default")
      (node (ref "SV3") (pin "16") (pinfunction "16_16") (pintype "passive"))
    )
    (net (code "118") (name "unconnected-(SV3-Pad18)") (class "Default")
      (node (ref "SV3") (pin "18") (pinfunction "18_18") (pintype "passive"))
    )
    (net (code "119") (name "unconnected-(SV3-Pad22)") (class "Default")
      (node (ref "SV3") (pin "22") (pinfunction "22_22") (pintype "passive"))
    )
    (net (code "120") (name "unconnected-(SV3-Pad29)") (class "Default")
      (node (ref "SV3") (pin "29") (pinfunction "29_29") (pintype "passive"))
    )
    (net (code "121") (name "unconnected-(SV3-Pad31)") (class "Default")
      (node (ref "SV3") (pin "31") (pinfunction "31_31") (pintype "passive"))
    )
    (net (code "122") (name "unconnected-(SV3-Pad32)") (class "Default")
      (node (ref "SV3") (pin "32") (pinfunction "32_32") (pintype "passive"))
    )
    (net (code "123") (name "unconnected-(SV3-Pad33)") (class "Default")
      (node (ref "SV3") (pin "33") (pinfunction "33_33") (pintype "passive"))
    )
    (net (code "124") (name "unconnected-(SV3-Pad35)") (class "Default")
      (node (ref "SV3") (pin "35") (pinfunction "35_35") (pintype "passive"))
    )
    (net (code "125") (name "unconnected-(SV3-Pad36)") (class "Default")
      (node (ref "SV3") (pin "36") (pinfunction "36_36") (pintype "passive"))
    )
    (net (code "126") (name "unconnected-(SV3-Pad38)") (class "Default")
      (node (ref "SV3") (pin "38") (pinfunction "38_38") (pintype "passive"))
    )
    (net (code "127") (name "unconnected-(SV3-Pad40)") (class "Default")
      (node (ref "SV3") (pin "40") (pinfunction "40_40") (pintype "passive"))
    )
    (net (code "128") (name "unconnected-(SV5-KEY-Pad7)") (class "Default")
      (node (ref "SV5") (pin "7") (pinfunction "KEY_7") (pintype "bidirectional"))
    )
    (net (code "129") (name "unconnected-(SV5-NC{slash}TDI-Pad8)") (class "Default")
      (node (ref "SV5") (pin "8") (pinfunction "NC/TDI_8") (pintype "bidirectional"))
    )
    (net (code "130") (name "unconnected-(SV5-SWO{slash}TDO-Pad6)") (class "Default")
      (node (ref "SV5") (pin "6") (pinfunction "SWO/TDO_6") (pintype "bidirectional"))
    )
    (net (code "131") (name "~{CAN_INT}") (class "Default")
      (node (ref "IC6") (pin "6") (pinfunction "PA0_6") (pintype "bidirectional"))
      (node (ref "SV3") (pin "37") (pinfunction "37_37") (pintype "passive"))
    )
    (net (code "132") (name "~{CORTEX_RST}") (class "Default")
      (node (ref "IC6") (pin "4") (pinfunction "~{RST}_4") (pintype "input"))
      (node (ref "SV5") (pin "10") (pinfunction "~{RESET}_10") (pintype "bidirectional"))
    )
    (net (code "133") (name "~{OUT_ENABLE}") (class "Default")
      (node (ref "IC2") (pin "12") (pinfunction "IO12_12") (pintype "bidirectional"))
      (node (ref "SV3") (pin "13") (pinfunction "13_13") (pintype "passive"))
    )
    (net (code "134") (name "~{OUT_RESET}") (class "Default")
      (node (ref "IC2") (pin "13") (pinfunction "IO13_13") (pintype "bidirectional"))
      (node (ref "SV3") (pin "11") (pinfunction "11_11") (pintype "passive"))
    )
    (net (code "135") (name "~{SPI_CS0}") (class "Default")
      (node (ref "IC2") (pin "4") (pinfunction "IO4_4") (pintype "bidirectional"))
      (node (ref "SV3") (pin "24") (pinfunction "24_24") (pintype "passive"))
    )
    (net (code "136") (name "~{SPI_CS1}") (class "Default")
      (node (ref "SV3") (pin "26") (pinfunction "26_26") (pintype "passive"))
    )
  )
)
